# STM32.net
KiCad netlist of a schematic drawn in Altium Designer
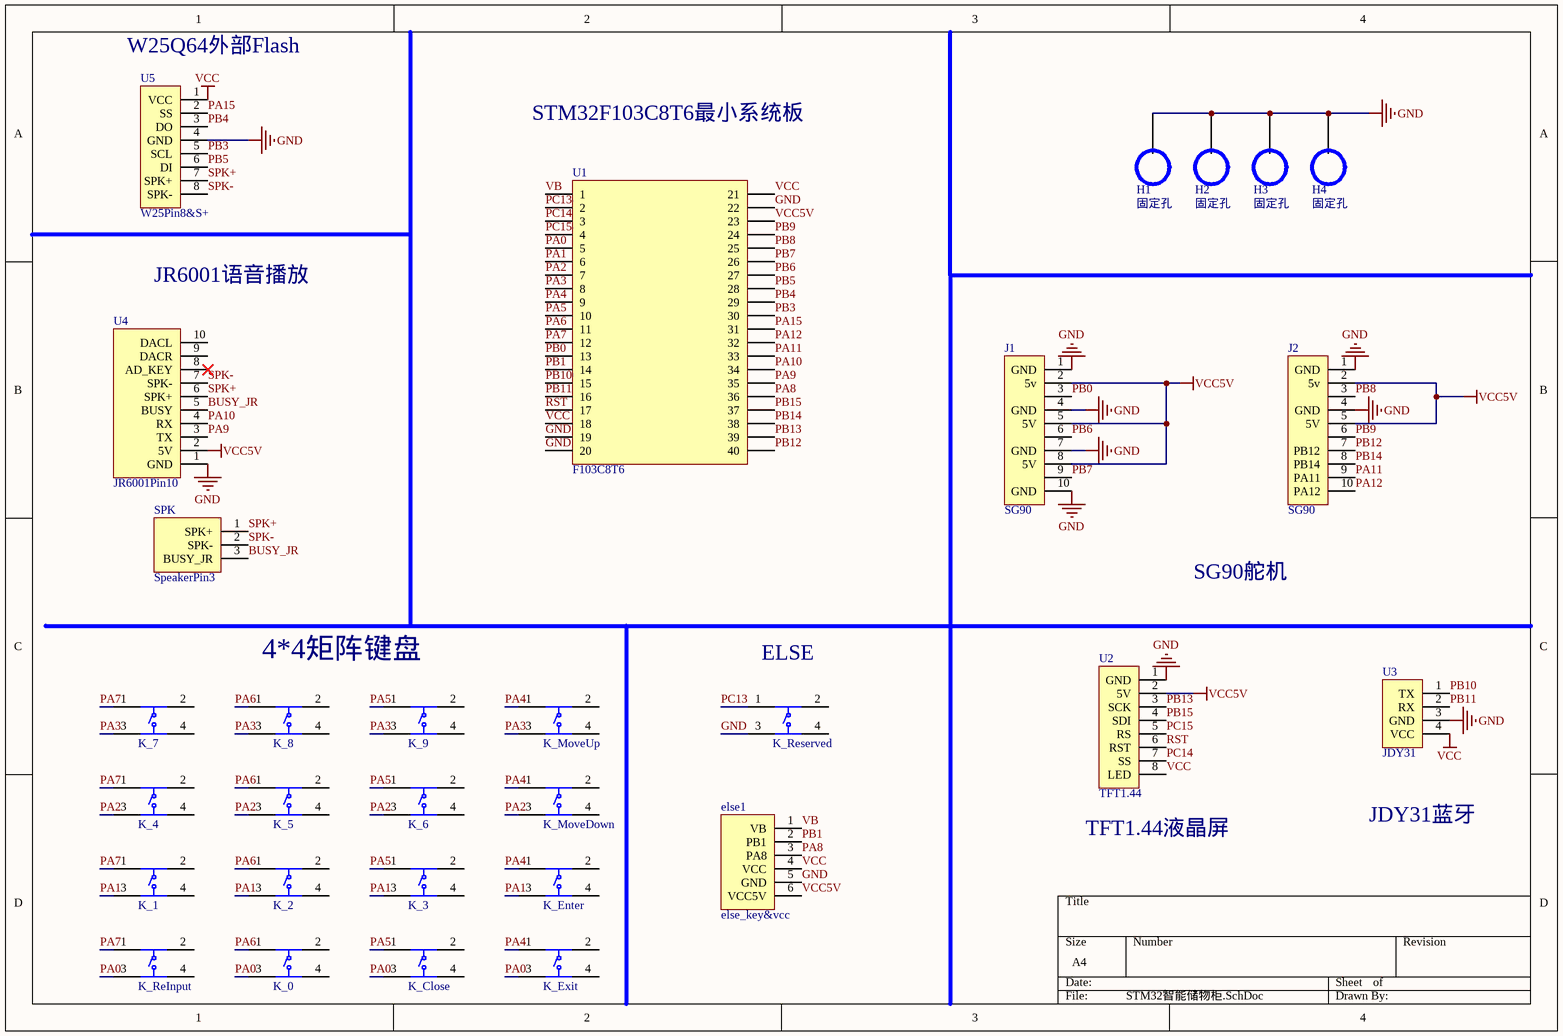
[diagram p0: STM32智能储物柜.SchDoc]

(export (version "E")
  (design (tool "Eeschema 10.0.6"))
  (components
    (comp (ref "else1")
      (value "else_key&vcc")
      (footprint "else2*3Pin")
      (libsource (lib "SchLib_GDesign") (part "else_key&vcc"))
    )
    (comp (ref "H1") (value "固定孔") (footprint "铜柱孔") (libsource (lib "SchLib_GDesign") (part "固定孔")))
    (comp (ref "H2") (value "固定孔") (footprint "铜柱孔") (libsource (lib "SchLib_GDesign") (part "固定孔")))
    (comp (ref "H3") (value "固定孔") (footprint "铜柱孔") (libsource (lib "SchLib_GDesign") (part "固定孔")))
    (comp (ref "H4") (value "固定孔") (footprint "铜柱孔") (libsource (lib "SchLib_GDesign") (part "固定孔")))
    (comp (ref "J1")
      (value "SG90")
      (footprint "SG90*3+1")
      (description "舵机")
      (libsource (lib "SchLib_GDesign") (part "SG90_1"))
    )
    (comp (ref "J2")
      (value "SG90")
      (footprint "SG90*2+4")
      (description "舵机")
      (libsource (lib "SchLib_GDesign") (part "SG90_2"))
    )
    (comp (ref "K_0")
      (value "TS665CJ")
      (footprint "SW-TH_4P-L6.0-W6.0-P4.50-LS6.5")
      (description "矩阵按键")
      (libsource (lib "SchLib_GDesign") (part "TS665CJ"))
    )
    (comp (ref "K_1")
      (value "TS665CJ")
      (footprint "SW-TH_4P-L6.0-W6.0-P4.50-LS6.5")
      (description "矩阵按键")
      (libsource (lib "SchLib_GDesign") (part "TS665CJ"))
    )
    (comp (ref "K_2")
      (value "TS665CJ")
      (footprint "SW-TH_4P-L6.0-W6.0-P4.50-LS6.5")
      (description "矩阵按键")
      (libsource (lib "SchLib_GDesign") (part "TS665CJ"))
    )
    (comp (ref "K_3")
      (value "TS665CJ")
      (footprint "SW-TH_4P-L6.0-W6.0-P4.50-LS6.5")
      (description "矩阵按键")
      (libsource (lib "SchLib_GDesign") (part "TS665CJ"))
    )
    (comp (ref "K_4")
      (value "TS665CJ")
      (footprint "SW-TH_4P-L6.0-W6.0-P4.50-LS6.5")
      (description "矩阵按键")
      (libsource (lib "SchLib_GDesign") (part "TS665CJ"))
    )
    (comp (ref "K_5")
      (value "TS665CJ")
      (footprint "SW-TH_4P-L6.0-W6.0-P4.50-LS6.5")
      (description "矩阵按键")
      (libsource (lib "SchLib_GDesign") (part "TS665CJ"))
    )
    (comp (ref "K_6")
      (value "TS665CJ")
      (footprint "SW-TH_4P-L6.0-W6.0-P4.50-LS6.5")
      (description "矩阵按键")
      (libsource (lib "SchLib_GDesign") (part "TS665CJ"))
    )
    (comp (ref "K_7")
      (value "TS665CJ")
      (footprint "SW-TH_4P-L6.0-W6.0-P4.50-LS6.5")
      (description "矩阵按键")
      (libsource (lib "SchLib_GDesign") (part "TS665CJ"))
    )
    (comp (ref "K_8")
      (value "TS665CJ")
      (footprint "SW-TH_4P-L6.0-W6.0-P4.50-LS6.5")
      (description "矩阵按键")
      (libsource (lib "SchLib_GDesign") (part "TS665CJ"))
    )
    (comp (ref "K_9")
      (value "TS665CJ")
      (footprint "SW-TH_4P-L6.0-W6.0-P4.50-LS6.5")
      (description "矩阵按键")
      (libsource (lib "SchLib_GDesign") (part "TS665CJ"))
    )
    (comp (ref "K_Close")
      (value "TS665CJ")
      (footprint "SW-TH_4P-L6.0-W6.0-P4.50-LS6.5")
      (description "矩阵按键")
      (libsource (lib "SchLib_GDesign") (part "TS665CJ"))
    )
    (comp (ref "K_Enter")
      (value "TS665CJ")
      (footprint "SW-TH_4P-L6.0-W6.0-P4.50-LS6.5")
      (description "矩阵按键")
      (libsource (lib "SchLib_GDesign") (part "TS665CJ"))
    )
    (comp (ref "K_Exit")
      (value "TS665CJ")
      (footprint "SW-TH_4P-L6.0-W6.0-P4.50-LS6.5")
      (description "矩阵按键")
      (libsource (lib "SchLib_GDesign") (part "TS665CJ"))
    )
    (comp (ref "K_MoveDown")
      (value "TS665CJ")
      (footprint "SW-TH_4P-L6.0-W6.0-P4.50-LS6.5")
      (description "矩阵按键")
      (libsource (lib "SchLib_GDesign") (part "TS665CJ"))
    )
    (comp (ref "K_MoveUp")
      (value "TS665CJ")
      (footprint "SW-TH_4P-L6.0-W6.0-P4.50-LS6.5")
      (description "矩阵按键")
      (libsource (lib "SchLib_GDesign") (part "TS665CJ"))
    )
    (comp (ref "K_ReInput")
      (value "TS665CJ")
      (footprint "SW-TH_4P-L6.0-W6.0-P4.50-LS6.5")
      (description "矩阵按键")
      (libsource (lib "SchLib_GDesign") (part "TS665CJ"))
    )
    (comp (ref "K_Reserved")
      (value "TS665CJ")
      (footprint "SW-TH_4P-L6.0-W6.0-P4.50-LS6.5")
      (description "矩阵按键")
      (libsource (lib "SchLib_GDesign") (part "TS665CJ"))
    )
    (comp (ref "SPK")
      (value "SpeakerPin3")
      (footprint "SpeakerPin3")
      (description "喇叭")
      (libsource (lib "SchLib_GDesign") (part "SpeakerPin3"))
    )
    (comp (ref "U1")
      (value "F103C8T6")
      (footprint "HDR2X20")
      (description "主控电路")
      (fields (field (name "PUBLISHER") "Altium Limited"))
      (libsource (lib "SchLib_GDesign") (part "Header2*20"))
    )
    (comp (ref "U2")
      (value "TFT1.44")
      (footprint "TFTPin8")
      (description "TFT液晶屏")
      (libsource (lib "SchLib_GDesign") (part "TFTPin8"))
    )
    (comp (ref "U3") (value "JDY31") (footprint "4PinJDY31") (libsource (lib "SchLib_GDesign") (part "4Pin")))
    (comp (ref "U4")
      (value "JR6001Pin10")
      (footprint "JR6001Pin10")
      (description "语音")
      (libsource (lib "SchLib_GDesign") (part "JR6001Pin10"))
    )
    (comp (ref "U5")
      (value "W25Pin8&S+")
      (footprint "W25Pin8&S+")
      (description "FLASH")
      (libsource (lib "SchLib_GDesign") (part "W25Pin8&S+"))
    )
  )
  (nets
    (net (code "1") (name "/BUSY_JR") (class "Default")
      (node (ref "SPK") (pin "3") (pinfunction "BUSY_JR_3") (pintype "passive"))
      (node (ref "U4") (pin "5") (pinfunction "BUSY_5") (pintype "passive"))
    )
    (net (code "2") (name "/PA0") (class "Default")
      (node (ref "K_0") (pin "3") (pinfunction "3_3") (pintype "passive"))
      (node (ref "K_Close") (pin "3") (pinfunction "3_3") (pintype "passive"))
      (node (ref "K_Exit") (pin "3") (pinfunction "3_3") (pintype "passive"))
      (node (ref "K_ReInput") (pin "3") (pinfunction "3_3") (pintype "passive"))
      (node (ref "U1") (pin "5") (pinfunction "5_5") (pintype "passive"))
    )
    (net (code "3") (name "/PA1") (class "Default")
      (node (ref "K_1") (pin "3") (pinfunction "3_3") (pintype "passive"))
      (node (ref "K_2") (pin "3") (pinfunction "3_3") (pintype "passive"))
      (node (ref "K_3") (pin "3") (pinfunction "3_3") (pintype "passive"))
      (node (ref "K_Enter") (pin "3") (pinfunction "3_3") (pintype "passive"))
      (node (ref "U1") (pin "6") (pinfunction "6_6") (pintype "passive"))
    )
    (net (code "4") (name "/PA2") (class "Default")
      (node (ref "K_4") (pin "3") (pinfunction "3_3") (pintype "passive"))
      (node (ref "K_5") (pin "3") (pinfunction "3_3") (pintype "passive"))
      (node (ref "K_6") (pin "3") (pinfunction "3_3") (pintype "passive"))
      (node (ref "K_MoveDown") (pin "3") (pinfunction "3_3") (pintype "passive"))
      (node (ref "U1") (pin "7") (pinfunction "7_7") (pintype "passive"))
    )
    (net (code "5") (name "/PA3") (class "Default")
      (node (ref "K_7") (pin "3") (pinfunction "3_3") (pintype "passive"))
      (node (ref "K_8") (pin "3") (pinfunction "3_3") (pintype "passive"))
      (node (ref "K_9") (pin "3") (pinfunction "3_3") (pintype "passive"))
      (node (ref "K_MoveUp") (pin "3") (pinfunction "3_3") (pintype "passive"))
      (node (ref "U1") (pin "8") (pinfunction "8_8") (pintype "passive"))
    )
    (net (code "6") (name "/PA4") (class "Default")
      (node (ref "K_Enter") (pin "1") (pinfunction "1_1") (pintype "passive"))
      (node (ref "K_Exit") (pin "1") (pinfunction "1_1") (pintype "passive"))
      (node (ref "K_MoveDown") (pin "1") (pinfunction "1_1") (pintype "passive"))
      (node (ref "K_MoveUp") (pin "1") (pinfunction "1_1") (pintype "passive"))
      (node (ref "U1") (pin "9") (pinfunction "9_9") (pintype "passive"))
    )
    (net (code "7") (name "/PA5") (class "Default")
      (node (ref "K_3") (pin "1") (pinfunction "1_1") (pintype "passive"))
      (node (ref "K_6") (pin "1") (pinfunction "1_1") (pintype "passive"))
      (node (ref "K_9") (pin "1") (pinfunction "1_1") (pintype "passive"))
      (node (ref "K_Close") (pin "1") (pinfunction "1_1") (pintype "passive"))
      (node (ref "U1") (pin "10") (pinfunction "10_10") (pintype "passive"))
    )
    (net (code "8") (name "/PA6") (class "Default")
      (node (ref "K_0") (pin "1") (pinfunction "1_1") (pintype "passive"))
      (node (ref "K_2") (pin "1") (pinfunction "1_1") (pintype "passive"))
      (node (ref "K_5") (pin "1") (pinfunction "1_1") (pintype "passive"))
      (node (ref "K_8") (pin "1") (pinfunction "1_1") (pintype "passive"))
      (node (ref "U1") (pin "11") (pinfunction "11_11") (pintype "passive"))
    )
    (net (code "9") (name "/PA7") (class "Default")
      (node (ref "K_1") (pin "1") (pinfunction "1_1") (pintype "passive"))
      (node (ref "K_4") (pin "1") (pinfunction "1_1") (pintype "passive"))
      (node (ref "K_7") (pin "1") (pinfunction "1_1") (pintype "passive"))
      (node (ref "K_ReInput") (pin "1") (pinfunction "1_1") (pintype "passive"))
      (node (ref "U1") (pin "12") (pinfunction "12_12") (pintype "passive"))
    )
    (net (code "10") (name "/PA8") (class "Default")
      (node (ref "U1") (pin "36") (pinfunction "36_36") (pintype "passive"))
      (node (ref "else1") (pin "3") (pinfunction "PA8_3") (pintype "passive"))
    )
    (net (code "11") (name "/PA9") (class "Default")
      (node (ref "U1") (pin "35") (pinfunction "35_35") (pintype "passive"))
      (node (ref "U4") (pin "3") (pinfunction "TX_3") (pintype "passive"))
    )
    (net (code "12") (name "/PA10") (class "Default")
      (node (ref "U1") (pin "34") (pinfunction "34_34") (pintype "passive"))
      (node (ref "U4") (pin "4") (pinfunction "RX_4") (pintype "passive"))
    )
    (net (code "13") (name "/PA11") (class "Default")
      (node (ref "J2") (pin "9") (pinfunction "PA11_9") (pintype "passive"))
      (node (ref "U1") (pin "33") (pinfunction "33_33") (pintype "passive"))
    )
    (net (code "14") (name "/PA12") (class "Default")
      (node (ref "J2") (pin "10") (pinfunction "PA12_10") (pintype "passive"))
      (node (ref "U1") (pin "32") (pinfunction "32_32") (pintype "passive"))
    )
    (net (code "15") (name "/PA15") (class "Default")
      (node (ref "U1") (pin "31") (pinfunction "31_31") (pintype "passive"))
      (node (ref "U5") (pin "2") (pinfunction "SS_2") (pintype "passive"))
    )
    (net (code "16") (name "/PB0") (class "Default")
      (node (ref "J1") (pin "3") (pintype "passive"))
      (node (ref "U1") (pin "13") (pinfunction "13_13") (pintype "passive"))
    )
    (net (code "17") (name "/PB1") (class "Default")
      (node (ref "U1") (pin "14") (pinfunction "14_14") (pintype "passive"))
      (node (ref "else1") (pin "2") (pinfunction "PB1_2") (pintype "passive"))
    )
    (net (code "18") (name "/PB3") (class "Default")
      (node (ref "U1") (pin "30") (pinfunction "30_30") (pintype "passive"))
      (node (ref "U5") (pin "5") (pinfunction "SCL_5") (pintype "passive"))
    )
    (net (code "19") (name "/PB4") (class "Default")
      (node (ref "U1") (pin "29") (pinfunction "29_29") (pintype "passive"))
      (node (ref "U5") (pin "3") (pinfunction "DO_3") (pintype "passive"))
    )
    (net (code "20") (name "/PB5") (class "Default")
      (node (ref "U1") (pin "28") (pinfunction "28_28") (pintype "passive"))
      (node (ref "U5") (pin "6") (pinfunction "DI_6") (pintype "passive"))
    )
    (net (code "21") (name "/PB6") (class "Default")
      (node (ref "J1") (pin "6") (pintype "passive"))
      (node (ref "U1") (pin "27") (pinfunction "27_27") (pintype "passive"))
    )
    (net (code "22") (name "/PB7") (class "Default")
      (node (ref "J1") (pin "9") (pintype "passive"))
      (node (ref "U1") (pin "26") (pinfunction "26_26") (pintype "passive"))
    )
    (net (code "23") (name "/PB8") (class "Default")
      (node (ref "J2") (pin "3") (pintype "passive"))
      (node (ref "U1") (pin "25") (pinfunction "25_25") (pintype "passive"))
    )
    (net (code "24") (name "/PB9") (class "Default")
      (node (ref "J2") (pin "6") (pintype "passive"))
      (node (ref "U1") (pin "24") (pinfunction "24_24") (pintype "passive"))
    )
    (net (code "25") (name "/PB10") (class "Default")
      (node (ref "U1") (pin "15") (pinfunction "15_15") (pintype "passive"))
      (node (ref "U3") (pin "1") (pinfunction "TX_1") (pintype "passive"))
    )
    (net (code "26") (name "/PB11") (class "Default")
      (node (ref "U1") (pin "16") (pinfunction "16_16") (pintype "passive"))
      (node (ref "U3") (pin "2") (pinfunction "RX_2") (pintype "passive"))
    )
    (net (code "27") (name "/PB12") (class "Default")
      (node (ref "J2") (pin "7") (pinfunction "PB12_7") (pintype "passive"))
      (node (ref "U1") (pin "40") (pinfunction "40_40") (pintype "passive"))
    )
    (net (code "28") (name "/PB13") (class "Default")
      (node (ref "U1") (pin "39") (pinfunction "39_39") (pintype "passive"))
      (node (ref "U2") (pin "3") (pinfunction "SCK_3") (pintype "passive"))
    )
    (net (code "29") (name "/PB14") (class "Default")
      (node (ref "J2") (pin "8") (pinfunction "PB14_8") (pintype "passive"))
      (node (ref "U1") (pin "38") (pinfunction "38_38") (pintype "passive"))
    )
    (net (code "30") (name "/PB15") (class "Default")
      (node (ref "U1") (pin "37") (pinfunction "37_37") (pintype "passive"))
      (node (ref "U2") (pin "4") (pinfunction "SDI_4") (pintype "passive"))
    )
    (net (code "31") (name "/PC13") (class "Default")
      (node (ref "K_Reserved") (pin "1") (pinfunction "1_1") (pintype "passive"))
      (node (ref "U1") (pin "2") (pinfunction "2_2") (pintype "passive"))
    )
    (net (code "32") (name "/PC14") (class "Default")
      (node (ref "U1") (pin "3") (pinfunction "3_3") (pintype "passive"))
      (node (ref "U2") (pin "7") (pinfunction "SS_7") (pintype "passive"))
    )
    (net (code "33") (name "/PC15") (class "Default")
      (node (ref "U1") (pin "4") (pinfunction "4_4") (pintype "passive"))
      (node (ref "U2") (pin "5") (pinfunction "RS_5") (pintype "passive"))
    )
    (net (code "34") (name "/RST") (class "Default")
      (node (ref "U1") (pin "17") (pinfunction "17_17") (pintype "passive"))
      (node (ref "U2") (pin "6") (pinfunction "RST_6") (pintype "passive"))
    )
    (net (code "35") (name "/SPK+") (class "Default")
      (node (ref "SPK") (pin "1") (pinfunction "SPK+_1") (pintype "passive"))
      (node (ref "U4") (pin "6") (pinfunction "SPK+_6") (pintype "passive"))
      (node (ref "U5") (pin "7") (pinfunction "SPK+_7") (pintype "passive"))
    )
    (net (code "36") (name "/SPK-") (class "Default")
      (node (ref "SPK") (pin "2") (pinfunction "SPK-_2") (pintype "passive"))
      (node (ref "U4") (pin "7") (pinfunction "SPK-_7") (pintype "passive"))
      (node (ref "U5") (pin "8") (pinfunction "SPK-_8") (pintype "passive"))
    )
    (net (code "37") (name "/VB") (class "Default")
      (node (ref "U1") (pin "1") (pinfunction "1_1") (pintype "passive"))
      (node (ref "else1") (pin "1") (pinfunction "VB_1") (pintype "passive"))
    )
    (net (code "38") (name "GND") (class "Default")
      (node (ref "H1") (pin "11") (pinfunction "11_11") (pintype "passive"))
      (node (ref "H2") (pin "11") (pinfunction "11_11") (pintype "passive"))
      (node (ref "H3") (pin "11") (pinfunction "11_11") (pintype "passive"))
      (node (ref "H4") (pin "11") (pinfunction "11_11") (pintype "passive"))
      (node (ref "J1") (pin "1") (pinfunction "GND_1") (pintype "passive"))
      (node (ref "J1") (pin "10") (pinfunction "GND_10") (pintype "passive"))
      (node (ref "J1") (pin "4") (pinfunction "GND_4") (pintype "passive"))
      (node (ref "J1") (pin "7") (pinfunction "GND_7") (pintype "passive"))
      (node (ref "J2") (pin "1") (pinfunction "GND_1") (pintype "passive"))
      (node (ref "J2") (pin "4") (pinfunction "GND_4") (pintype "passive"))
      (node (ref "K_Reserved") (pin "3") (pinfunction "3_3") (pintype "passive"))
      (node (ref "U1") (pin "19") (pinfunction "19_19") (pintype "passive"))
      (node (ref "U1") (pin "20") (pinfunction "20_20") (pintype "passive"))
      (node (ref "U1") (pin "22") (pinfunction "22_22") (pintype "passive"))
      (node (ref "U2") (pin "1") (pinfunction "GND_1") (pintype "passive"))
      (node (ref "U3") (pin "3") (pinfunction "GND_3") (pintype "passive"))
      (node (ref "U4") (pin "1") (pinfunction "GND_1") (pintype "passive"))
      (node (ref "U5") (pin "4") (pinfunction "GND_4") (pintype "passive"))
      (node (ref "else1") (pin "5") (pinfunction "GND_5") (pintype "passive"))
    )
    (net (code "39") (name "VCC") (class "Default")
      (node (ref "U1") (pin "18") (pinfunction "18_18") (pintype "passive"))
      (node (ref "U1") (pin "21") (pinfunction "21_21") (pintype "passive"))
      (node (ref "U2") (pin "8") (pinfunction "LED_8") (pintype "passive"))
      (node (ref "U3") (pin "4") (pinfunction "VCC_4") (pintype "passive"))
      (node (ref "U5") (pin "1") (pinfunction "VCC_1") (pintype "passive"))
      (node (ref "else1") (pin "4") (pinfunction "VCC_4") (pintype "passive"))
    )
    (net (code "40") (name "VCC5V") (class "Default")
      (node (ref "J1") (pin "2") (pinfunction "5v_2") (pintype "passive"))
      (node (ref "J1") (pin "5") (pinfunction "5V_5") (pintype "passive"))
      (node (ref "J1") (pin "8") (pinfunction "5V_8") (pintype "passive"))
      (node (ref "J2") (pin "2") (pinfunction "5v_2") (pintype "passive"))
      (node (ref "J2") (pin "5") (pinfunction "5V_5") (pintype "passive"))
      (node (ref "U1") (pin "23") (pinfunction "23_23") (pintype "passive"))
      (node (ref "U2") (pin "2") (pinfunction "5V_2") (pintype "passive"))
      (node (ref "U4") (pin "2") (pinfunction "5V_2") (pintype "passive"))
      (node (ref "else1") (pin "6") (pinfunction "VCC5V_6") (pintype "passive"))
    )
    (net (code "41") (name "unconnected-(K_0-Pad2)") (class "Default")
      (node (ref "K_0") (pin "2") (pinfunction "2_2") (pintype "passive"))
    )
    (net (code "42") (name "unconnected-(K_0-Pad4)") (class "Default")
      (node (ref "K_0") (pin "4") (pinfunction "4_4") (pintype "passive"))
    )
    (net (code "43") (name "unconnected-(K_1-Pad2)") (class "Default")
      (node (ref "K_1") (pin "2") (pinfunction "2_2") (pintype "passive"))
    )
    (net (code "44") (name "unconnected-(K_1-Pad4)") (class "Default")
      (node (ref "K_1") (pin "4") (pinfunction "4_4") (pintype "passive"))
    )
    (net (code "45") (name "unconnected-(K_2-Pad2)") (class "Default")
      (node (ref "K_2") (pin "2") (pinfunction "2_2") (pintype "passive"))
    )
    (net (code "46") (name "unconnected-(K_2-Pad4)") (class "Default")
      (node (ref "K_2") (pin "4") (pinfunction "4_4") (pintype "passive"))
    )
    (net (code "47") (name "unconnected-(K_3-Pad2)") (class "Default")
      (node (ref "K_3") (pin "2") (pinfunction "2_2") (pintype "passive"))
    )
    (net (code "48") (name "unconnected-(K_3-Pad4)") (class "Default")
      (node (ref "K_3") (pin "4") (pinfunction "4_4") (pintype "passive"))
    )
    (net (code "49") (name "unconnected-(K_4-Pad2)") (class "Default")
      (node (ref "K_4") (pin "2") (pinfunction "2_2") (pintype "passive"))
    )
    (net (code "50") (name "unconnected-(K_4-Pad4)") (class "Default")
      (node (ref "K_4") (pin "4") (pinfunction "4_4") (pintype "passive"))
    )
    (net (code "51") (name "unconnected-(K_5-Pad2)") (class "Default")
      (node (ref "K_5") (pin "2") (pinfunction "2_2") (pintype "passive"))
    )
    (net (code "52") (name "unconnected-(K_5-Pad4)") (class "Default")
      (node (ref "K_5") (pin "4") (pinfunction "4_4") (pintype "passive"))
    )
    (net (code "53") (name "unconnected-(K_6-Pad2)") (class "Default")
      (node (ref "K_6") (pin "2") (pinfunction "2_2") (pintype "passive"))
    )
    (net (code "54") (name "unconnected-(K_6-Pad4)") (class "Default")
      (node (ref "K_6") (pin "4") (pinfunction "4_4") (pintype "passive"))
    )
    (net (code "55") (name "unconnected-(K_7-Pad2)") (class "Default")
      (node (ref "K_7") (pin "2") (pinfunction "2_2") (pintype "passive"))
    )
    (net (code "56") (name "unconnected-(K_7-Pad4)") (class "Default")
      (node (ref "K_7") (pin "4") (pinfunction "4_4") (pintype "passive"))
    )
    (net (code "57") (name "unconnected-(K_8-Pad2)") (class "Default")
      (node (ref "K_8") (pin "2") (pinfunction "2_2") (pintype "passive"))
    )
    (net (code "58") (name "unconnected-(K_8-Pad4)") (class "Default")
      (node (ref "K_8") (pin "4") (pinfunction "4_4") (pintype "passive"))
    )
    (net (code "59") (name "unconnected-(K_9-Pad2)") (class "Default")
      (node (ref "K_9") (pin "2") (pinfunction "2_2") (pintype "passive"))
    )
    (net (code "60") (name "unconnected-(K_9-Pad4)") (class "Default")
      (node (ref "K_9") (pin "4") (pinfunction "4_4") (pintype "passive"))
    )
    (net (code "61") (name "unconnected-(K_Close-Pad2)") (class "Default")
      (node (ref "K_Close") (pin "2") (pinfunction "2_2") (pintype "passive"))
    )
    (net (code "62") (name "unconnected-(K_Close-Pad4)") (class "Default")
      (node (ref "K_Close") (pin "4") (pinfunction "4_4") (pintype "passive"))
    )
    (net (code "63") (name "unconnected-(K_Enter-Pad2)") (class "Default")
      (node (ref "K_Enter") (pin "2") (pinfunction "2_2") (pintype "passive"))
    )
    (net (code "64") (name "unconnected-(K_Enter-Pad4)") (class "Default")
      (node (ref "K_Enter") (pin "4") (pinfunction "4_4") (pintype "passive"))
    )
    (net (code "65") (name "unconnected-(K_Exit-Pad2)") (class "Default")
      (node (ref "K_Exit") (pin "2") (pinfunction "2_2") (pintype "passive"))
    )
    (net (code "66") (name "unconnected-(K_Exit-Pad4)") (class "Default")
      (node (ref "K_Exit") (pin "4") (pinfunction "4_4") (pintype "passive"))
    )
    (net (code "67") (name "unconnected-(K_MoveDown-Pad2)") (class "Default")
      (node (ref "K_MoveDown") (pin "2") (pinfunction "2_2") (pintype "passive"))
    )
    (net (code "68") (name "unconnected-(K_MoveDown-Pad4)") (class "Default")
      (node (ref "K_MoveDown") (pin "4") (pinfunction "4_4") (pintype "passive"))
    )
    (net (code "69") (name "unconnected-(K_MoveUp-Pad2)") (class "Default")
      (node (ref "K_MoveUp") (pin "2") (pinfunction "2_2") (pintype "passive"))
    )
    (net (code "70") (name "unconnected-(K_MoveUp-Pad4)") (class "Default")
      (node (ref "K_MoveUp") (pin "4") (pinfunction "4_4") (pintype "passive"))
    )
    (net (code "71") (name "unconnected-(K_ReInput-Pad2)") (class "Default")
      (node (ref "K_ReInput") (pin "2") (pinfunction "2_2") (pintype "passive"))
    )
    (net (code "72") (name "unconnected-(K_ReInput-Pad4)") (class "Default")
      (node (ref "K_ReInput") (pin "4") (pinfunction "4_4") (pintype "passive"))
    )
    (net (code "73") (name "unconnected-(K_Reserved-Pad2)") (class "Default")
      (node (ref "K_Reserved") (pin "2") (pinfunction "2_2") (pintype "passive"))
    )
    (net (code "74") (name "unconnected-(K_Reserved-Pad4)") (class "Default")
      (node (ref "K_Reserved") (pin "4") (pinfunction "4_4") (pintype "passive"))
    )
    (net (code "75") (name "unconnected-(U4-AD_KEY-Pad8)") (class "Default")
      (node (ref "U4") (pin "8") (pinfunction "AD_KEY_8") (pintype "passive+no_connect"))
    )
    (net (code "76") (name "unconnected-(U4-DACL-Pad10)") (class "Default")
      (node (ref "U4") (pin "10") (pinfunction "DACL_10") (pintype "passive"))
    )
    (net (code "77") (name "unconnected-(U4-DACR-Pad9)") (class "Default")
      (node (ref "U4") (pin "9") (pinfunction "DACR_9") (pintype "passive"))
    )
  )
)
